# Power_Board_5V.net
KiCad netlist of a schematic drawn in Altium Designer
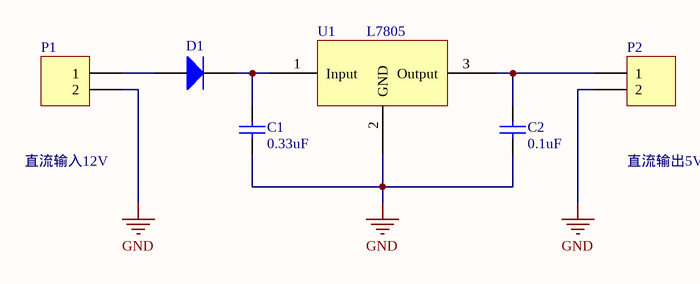
[diagram p0: Power_Board_5V.SchDoc]

(export (version "E")
  (design (tool "Eeschema 10.0.6"))
  (components
    (comp (ref "C1")
      (value "0.33uF")
      (footprint "RAD-0.3")
      (description "Capacitor")
      (fields (field (name "Comment") "Cap") (field (name "PUBLISHER") "Altium Limited"))
      (libsource (lib "Miscellaneous Devices") (part "Cap"))
    )
    (comp (ref "C2")
      (value "0.1uF")
      (footprint "RAD-0.3")
      (description "Capacitor")
      (fields (field (name "Comment") "Cap") (field (name "PUBLISHER") "Altium Limited"))
      (libsource (lib "Miscellaneous Devices") (part "Cap"))
    )
    (comp (ref "D1")
      (value "Diode")
      (footprint "SMC")
      (description "Default Diode")
      (fields (field (name "PUBLISHER") "Altium Limited"))
      (libsource (lib "Miscellaneous Devices") (part "Diode"))
    )
    (comp (ref "P1")
      (value "Header 2")
      (footprint "HDR1X2")
      (description "Header, 2-Pin")
      (fields (field (name "PUBLISHER") "Altium Limited"))
      (libsource (lib "Miscellaneous Connectors") (part "Header 2"))
    )
    (comp (ref "P2")
      (value "Header 2")
      (footprint "HDR1X2")
      (description "Header, 2-Pin")
      (fields (field (name "PUBLISHER") "Altium Limited"))
      (libsource (lib "") (part "Header 2_1"))
    )
    (comp (ref "U1") (value "L7805") (libsource (lib "Yi Ping_Schlib") (part "L7805")))
  )
  (nets
    (net (code "1") (name "GND") (class "Default")
      (node (ref "C1") (pin "1") (pinfunction "1_1") (pintype "passive"))
      (node (ref "C2") (pin "1") (pinfunction "1_1") (pintype "passive"))
      (node (ref "P1") (pin "2") (pinfunction "2_2") (pintype "passive"))
      (node (ref "P2") (pin "2") (pinfunction "2_2") (pintype "passive"))
      (node (ref "U1") (pin "2") (pinfunction "GND_2") (pintype "passive"))
    )
    (net (code "2") (name "Net-(D1-A)") (class "Default")
      (node (ref "D1") (pin "1") (pinfunction "A_1") (pintype "passive"))
      (node (ref "P1") (pin "1") (pinfunction "1_1") (pintype "passive"))
    )
    (net (code "3") (name "Net-(D1-K)") (class "Default")
      (node (ref "C1") (pin "2") (pinfunction "2_2") (pintype "passive"))
      (node (ref "D1") (pin "2") (pinfunction "K_2") (pintype "passive"))
      (node (ref "U1") (pin "1") (pinfunction "Input_1") (pintype "passive"))
    )
    (net (code "4") (name "Net-(U1-Output)") (class "Default")
      (node (ref "C2") (pin "2") (pinfunction "2_2") (pintype "passive"))
      (node (ref "P2") (pin "1") (pinfunction "1_1") (pintype "passive"))
      (node (ref "U1") (pin "3") (pinfunction "Output_3") (pintype "passive"))
    )
  )
)
